# OCC_Test-_RailCom.net
KiCad netlist of a schematic drawn in EasyEDA
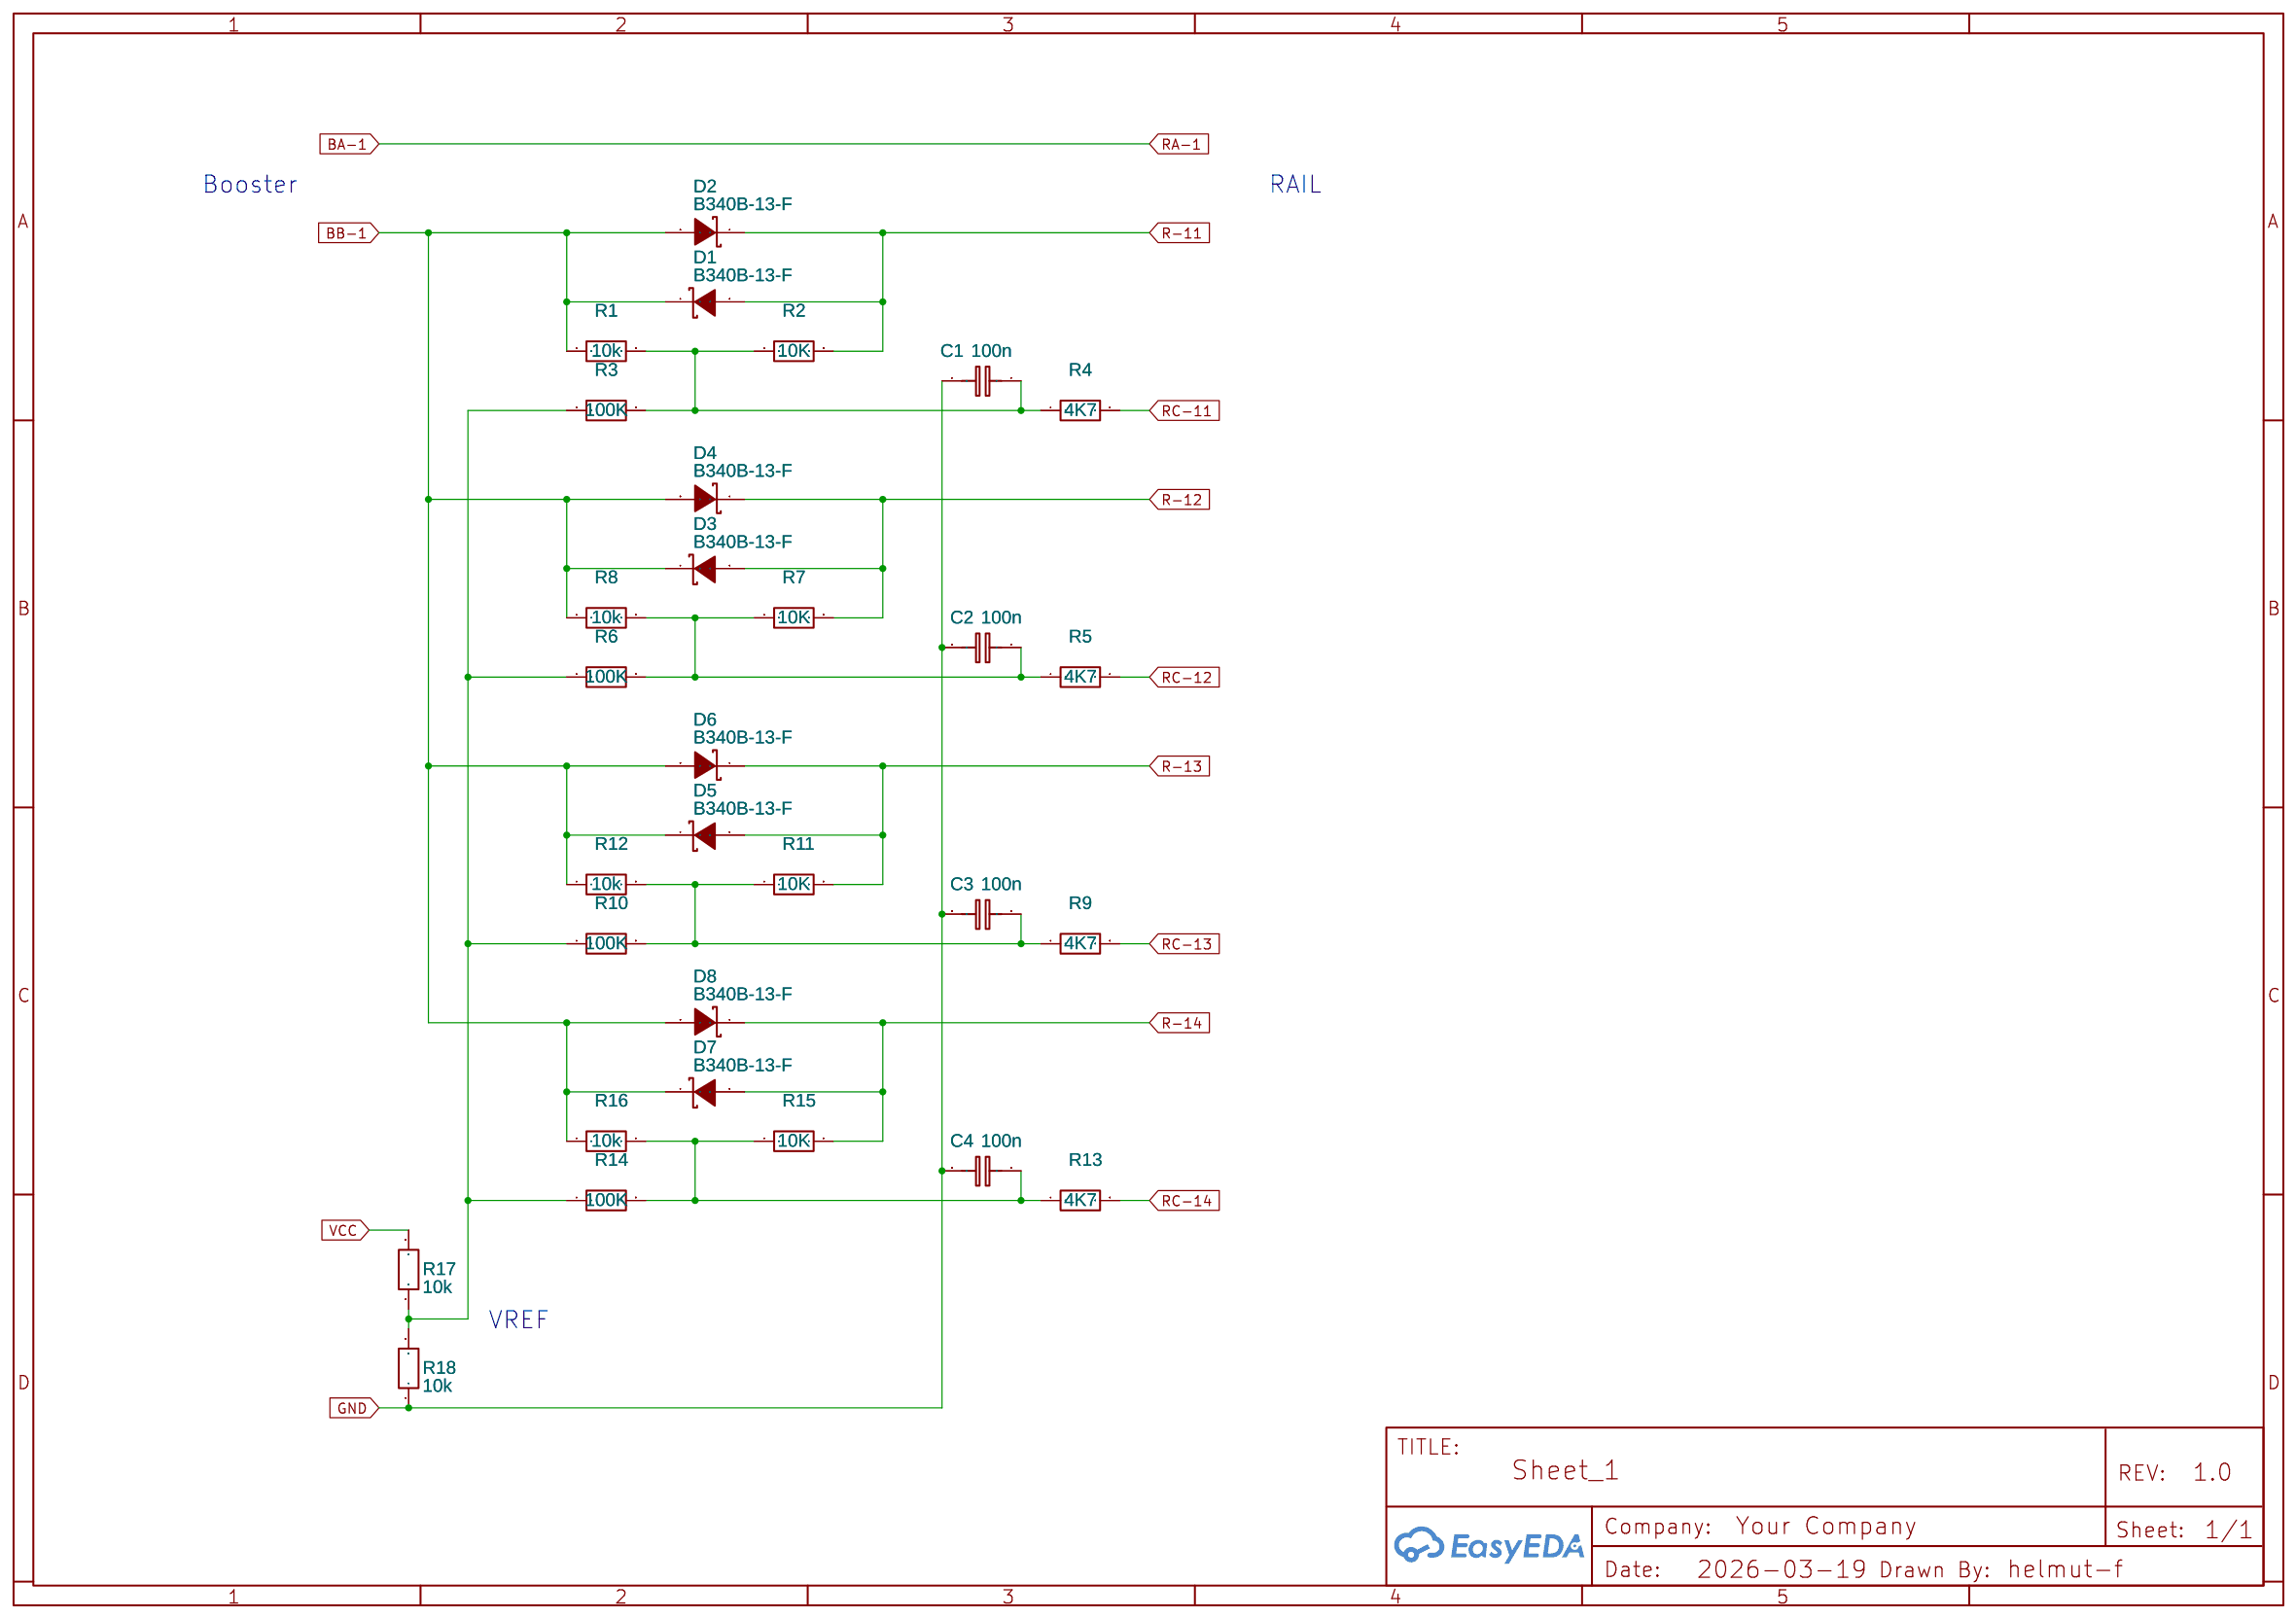
[diagram p0: schematic sheet]

(export (version "E")
  (design (tool "Eeschema 10.0.6"))
  (components
    (comp (ref "C1") (value "100n") (libsource (lib "") (part "C_1206_EU_1")))
    (comp (ref "C2") (value "100n") (libsource (lib "") (part "C_1206_EU")))
    (comp (ref "C3") (value "100n") (libsource (lib "") (part "C_1206_EU")))
    (comp (ref "C4") (value "100n") (libsource (lib "") (part "C_1206_EU")))
    (comp (ref "D1")
      (value "B340B-13-F")
      (fields (field (name "Manufacturer") "DIODES(美台)"))
      (libsource (lib "") (part "B340B-13-F"))
    )
    (comp (ref "D2")
      (value "B340B-13-F")
      (fields (field (name "Manufacturer") "DIODES(美台)"))
      (libsource (lib "") (part "B340B-13-F_1"))
    )
    (comp (ref "D3")
      (value "B340B-13-F")
      (fields (field (name "Manufacturer") "DIODES(美台)"))
      (libsource (lib "") (part "B340B-13-F"))
    )
    (comp (ref "D4")
      (value "B340B-13-F")
      (fields (field (name "Manufacturer") "DIODES(美台)"))
      (libsource (lib "") (part "B340B-13-F_1"))
    )
    (comp (ref "D5")
      (value "B340B-13-F")
      (fields (field (name "Manufacturer") "DIODES(美台)"))
      (libsource (lib "") (part "B340B-13-F"))
    )
    (comp (ref "D6")
      (value "B340B-13-F")
      (fields (field (name "Manufacturer") "DIODES(美台)"))
      (libsource (lib "") (part "B340B-13-F_1"))
    )
    (comp (ref "D7")
      (value "B340B-13-F")
      (fields (field (name "Manufacturer") "DIODES(美台)"))
      (libsource (lib "") (part "B340B-13-F"))
    )
    (comp (ref "D8")
      (value "B340B-13-F")
      (fields (field (name "Manufacturer") "DIODES(美台)"))
      (libsource (lib "") (part "B340B-13-F_1"))
    )
    (comp (ref "R1") (value "10k") (libsource (lib "") (part "R_1206_EU")))
    (comp (ref "R2") (value "10K") (libsource (lib "") (part "R_1206_EU")))
    (comp (ref "R3") (value "100K") (libsource (lib "") (part "R_1206_EU")))
    (comp (ref "R4") (value "4K7") (libsource (lib "") (part "R_1206_EU")))
    (comp (ref "R5") (value "4K7") (libsource (lib "") (part "R_1206_EU")))
    (comp (ref "R6") (value "100K") (libsource (lib "") (part "R_1206_EU")))
    (comp (ref "R7") (value "10K") (libsource (lib "") (part "R_1206_EU")))
    (comp (ref "R8") (value "10k") (libsource (lib "") (part "R_1206_EU")))
    (comp (ref "R9") (value "4K7") (libsource (lib "") (part "R_1206_EU")))
    (comp (ref "R10") (value "100K") (libsource (lib "") (part "R_1206_EU")))
    (comp (ref "R11") (value "10K") (libsource (lib "") (part "R_1206_EU")))
    (comp (ref "R12") (value "10k") (libsource (lib "") (part "R_1206_EU")))
    (comp (ref "R13") (value "4K7") (libsource (lib "") (part "R_1206_EU")))
    (comp (ref "R14") (value "100K") (libsource (lib "") (part "R_1206_EU")))
    (comp (ref "R15") (value "10K") (libsource (lib "") (part "R_1206_EU")))
    (comp (ref "R16") (value "10k") (libsource (lib "") (part "R_1206_EU")))
    (comp (ref "R17") (value "10k") (libsource (lib "") (part "R_1206_EU_1")))
    (comp (ref "R18") (value "10k") (libsource (lib "") (part "R_1206_EU_1")))
  )
  (nets
    (net (code "2") (name "BB-1") (class "Default")
      (node (ref "D1") (pin "1") (pinfunction "K_1") (pintype "unspecified"))
      (node (ref "D2") (pin "2") (pinfunction "A_2") (pintype "unspecified"))
      (node (ref "D3") (pin "1") (pinfunction "K_1") (pintype "unspecified"))
      (node (ref "D4") (pin "2") (pinfunction "A_2") (pintype "unspecified"))
      (node (ref "D5") (pin "1") (pinfunction "K_1") (pintype "unspecified"))
      (node (ref "D6") (pin "2") (pinfunction "A_2") (pintype "unspecified"))
      (node (ref "D7") (pin "1") (pinfunction "K_1") (pintype "unspecified"))
      (node (ref "D8") (pin "2") (pinfunction "A_2") (pintype "unspecified"))
      (node (ref "R1") (pin "1") (pinfunction "1_1") (pintype "unspecified"))
      (node (ref "R12") (pin "1") (pinfunction "1_1") (pintype "unspecified"))
      (node (ref "R16") (pin "1") (pinfunction "1_1") (pintype "unspecified"))
      (node (ref "R8") (pin "1") (pinfunction "1_1") (pintype "unspecified"))
    )
    (net (code "3") (name "GND") (class "Default")
      (node (ref "C1") (pin "2") (pinfunction "2_2") (pintype "unspecified"))
      (node (ref "C2") (pin "2") (pinfunction "2_2") (pintype "unspecified"))
      (node (ref "C3") (pin "2") (pinfunction "2_2") (pintype "unspecified"))
      (node (ref "C4") (pin "2") (pinfunction "2_2") (pintype "unspecified"))
      (node (ref "R18") (pin "1") (pinfunction "1_1") (pintype "unspecified"))
    )
    (net (code "4") (name "Net-(C1-Pad1)") (class "Default")
      (node (ref "C1") (pin "1") (pinfunction "1_1") (pintype "unspecified"))
      (node (ref "R1") (pin "2") (pinfunction "2_2") (pintype "unspecified"))
      (node (ref "R2") (pin "1") (pinfunction "1_1") (pintype "unspecified"))
      (node (ref "R3") (pin "2") (pinfunction "2_2") (pintype "unspecified"))
      (node (ref "R4") (pin "1") (pinfunction "1_1") (pintype "unspecified"))
    )
    (net (code "5") (name "Net-(C2-Pad1)") (class "Default")
      (node (ref "C2") (pin "1") (pinfunction "1_1") (pintype "unspecified"))
      (node (ref "R5") (pin "1") (pinfunction "1_1") (pintype "unspecified"))
      (node (ref "R6") (pin "2") (pinfunction "2_2") (pintype "unspecified"))
      (node (ref "R7") (pin "1") (pinfunction "1_1") (pintype "unspecified"))
      (node (ref "R8") (pin "2") (pinfunction "2_2") (pintype "unspecified"))
    )
    (net (code "6") (name "Net-(C3-Pad1)") (class "Default")
      (node (ref "C3") (pin "1") (pinfunction "1_1") (pintype "unspecified"))
      (node (ref "R10") (pin "2") (pinfunction "2_2") (pintype "unspecified"))
      (node (ref "R11") (pin "1") (pinfunction "1_1") (pintype "unspecified"))
      (node (ref "R12") (pin "2") (pinfunction "2_2") (pintype "unspecified"))
      (node (ref "R9") (pin "1") (pinfunction "1_1") (pintype "unspecified"))
    )
    (net (code "7") (name "Net-(C4-Pad1)") (class "Default")
      (node (ref "C4") (pin "1") (pinfunction "1_1") (pintype "unspecified"))
      (node (ref "R13") (pin "1") (pinfunction "1_1") (pintype "unspecified"))
      (node (ref "R14") (pin "2") (pinfunction "2_2") (pintype "unspecified"))
      (node (ref "R15") (pin "1") (pinfunction "1_1") (pintype "unspecified"))
      (node (ref "R16") (pin "2") (pinfunction "2_2") (pintype "unspecified"))
    )
    (net (code "8") (name "Net-(R10-Pad1)") (class "Default")
      (node (ref "R10") (pin "1") (pinfunction "1_1") (pintype "unspecified"))
      (node (ref "R14") (pin "1") (pinfunction "1_1") (pintype "unspecified"))
      (node (ref "R17") (pin "1") (pinfunction "1_1") (pintype "unspecified"))
      (node (ref "R18") (pin "2") (pinfunction "2_2") (pintype "unspecified"))
      (node (ref "R3") (pin "1") (pinfunction "1_1") (pintype "unspecified"))
      (node (ref "R6") (pin "1") (pinfunction "1_1") (pintype "unspecified"))
    )
    (net (code "9") (name "R-11") (class "Default")
      (node (ref "D1") (pin "2") (pinfunction "A_2") (pintype "unspecified"))
      (node (ref "D2") (pin "1") (pinfunction "K_1") (pintype "unspecified"))
      (node (ref "R2") (pin "2") (pinfunction "2_2") (pintype "unspecified"))
    )
    (net (code "10") (name "R-12") (class "Default")
      (node (ref "D3") (pin "2") (pinfunction "A_2") (pintype "unspecified"))
      (node (ref "D4") (pin "1") (pinfunction "K_1") (pintype "unspecified"))
      (node (ref "R7") (pin "2") (pinfunction "2_2") (pintype "unspecified"))
    )
    (net (code "11") (name "R-13") (class "Default")
      (node (ref "D5") (pin "2") (pinfunction "A_2") (pintype "unspecified"))
      (node (ref "D6") (pin "1") (pinfunction "K_1") (pintype "unspecified"))
      (node (ref "R11") (pin "2") (pinfunction "2_2") (pintype "unspecified"))
    )
    (net (code "12") (name "R-14") (class "Default")
      (node (ref "D7") (pin "2") (pinfunction "A_2") (pintype "unspecified"))
      (node (ref "D8") (pin "1") (pinfunction "K_1") (pintype "unspecified"))
      (node (ref "R15") (pin "2") (pinfunction "2_2") (pintype "unspecified"))
    )
    (net (code "13") (name "RC-11") (class "Default")
      (node (ref "R4") (pin "2") (pinfunction "2_2") (pintype "unspecified"))
    )
    (net (code "14") (name "RC-12") (class "Default")
      (node (ref "R5") (pin "2") (pinfunction "2_2") (pintype "unspecified"))
    )
    (net (code "15") (name "RC-13") (class "Default")
      (node (ref "R9") (pin "2") (pinfunction "2_2") (pintype "unspecified"))
    )
    (net (code "16") (name "RC-14") (class "Default")
      (node (ref "R13") (pin "2") (pinfunction "2_2") (pintype "unspecified"))
    )
    (net (code "17") (name "VCC") (class "Default")
      (node (ref "R17") (pin "2") (pinfunction "2_2") (pintype "unspecified"))
    )
  )
)
